# PCB_WiFiModule_to_Xbee_rev0_2.net
KiCad netlist of a schematic drawn in EAGLE
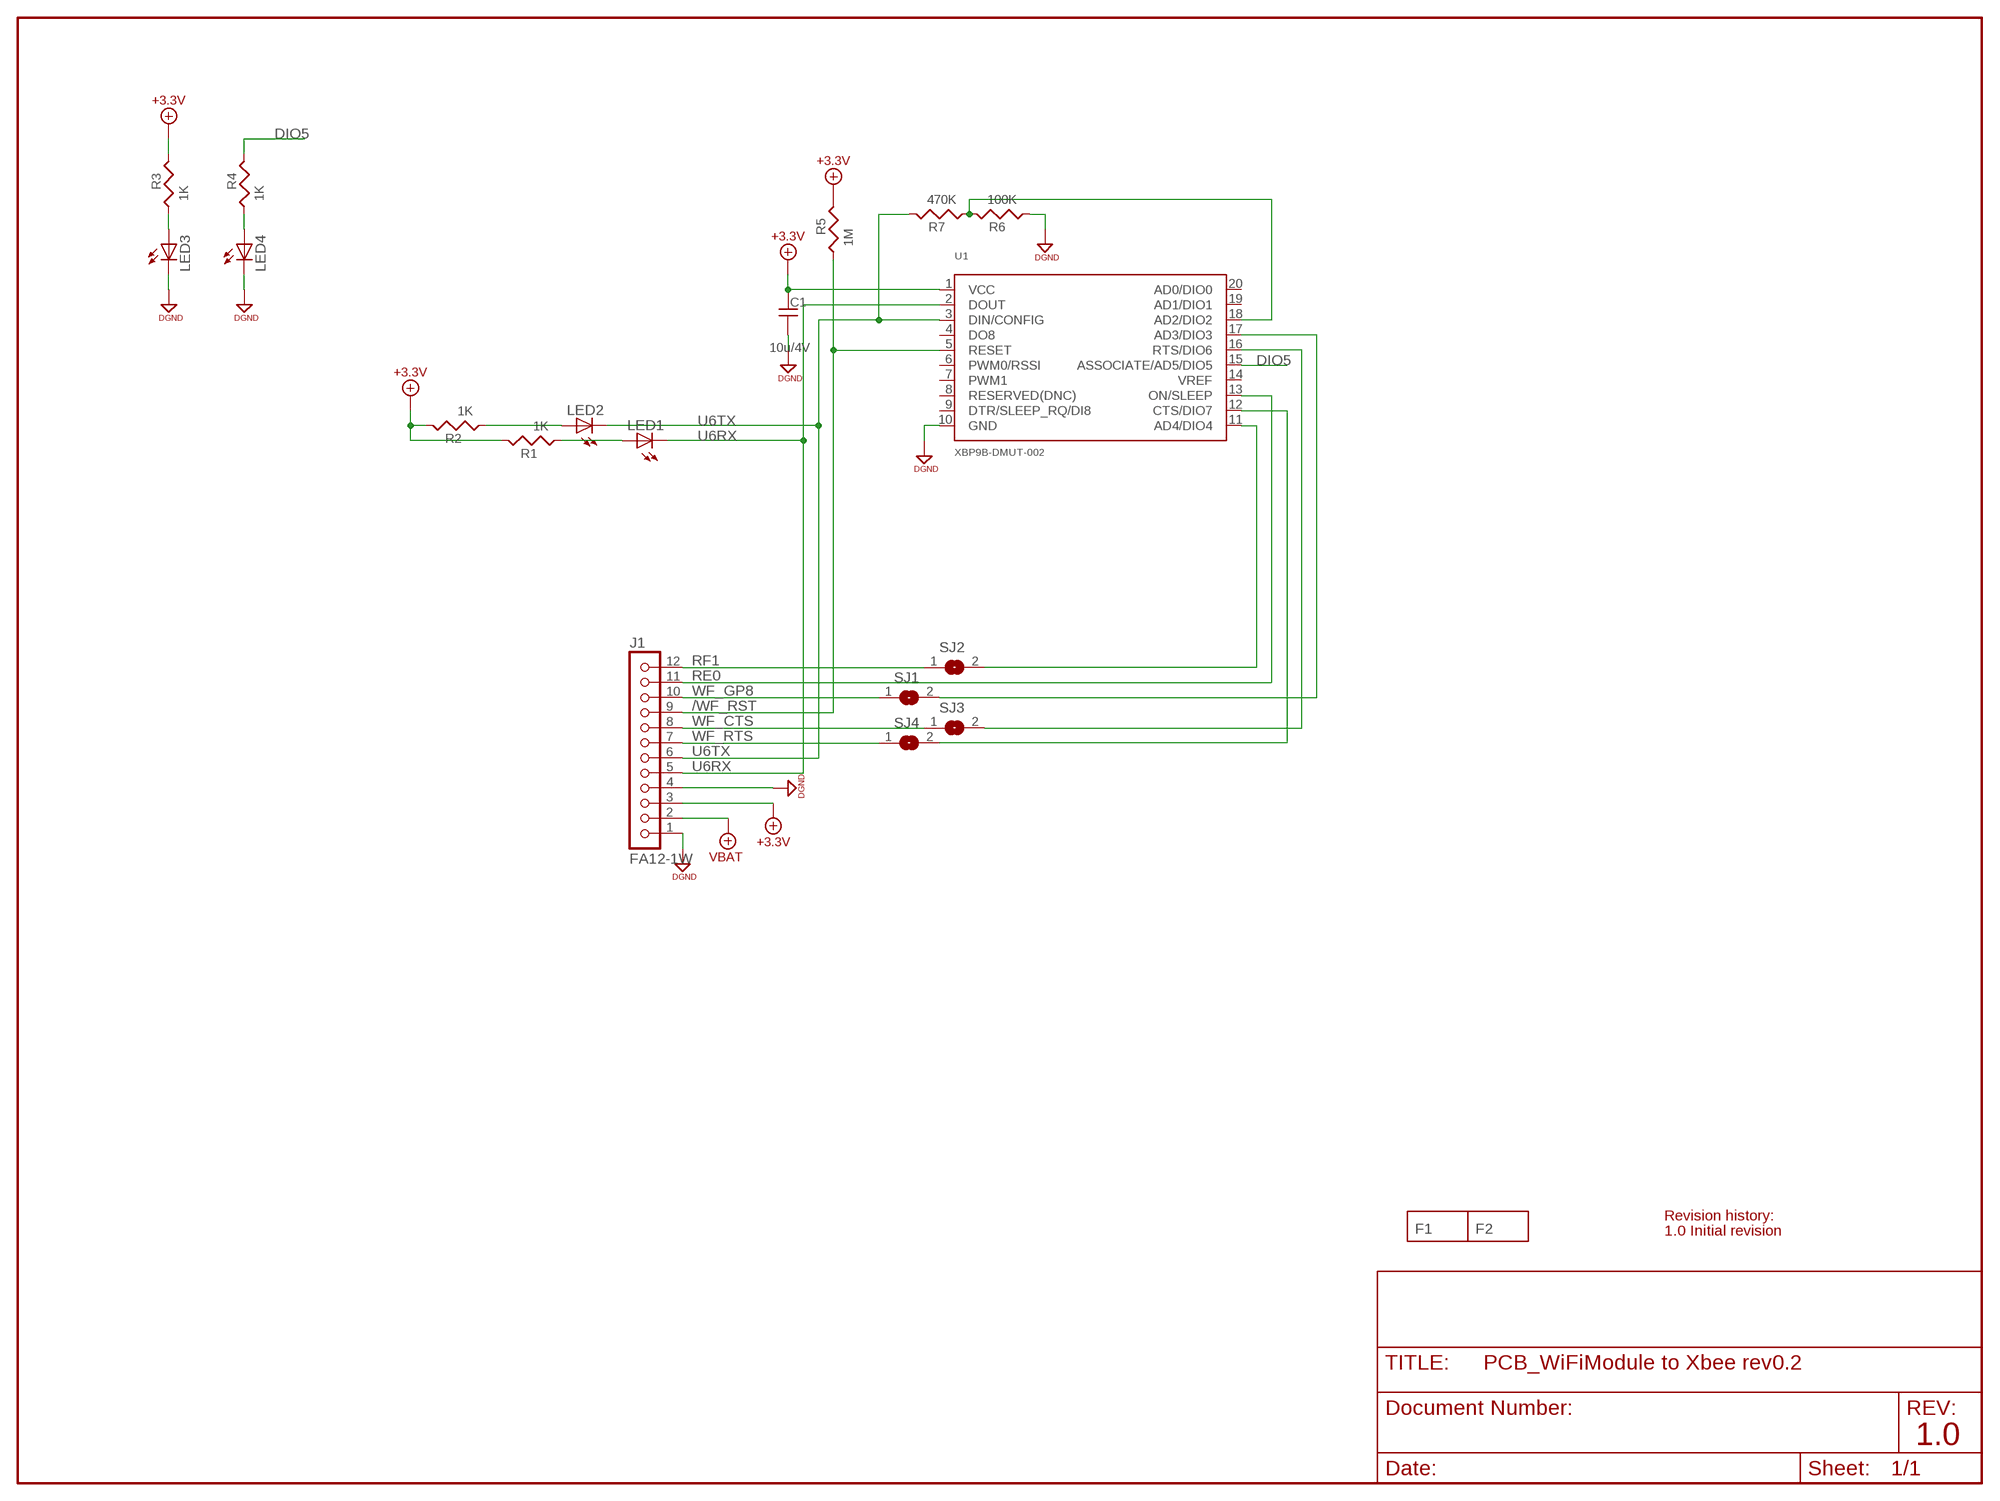
[diagram p0: schematic, sheet 1]

(export (version "E")
  (design (tool "Eeschema 10.0.6"))
  (components
    (comp (ref "C1")
      (value "10u/4V")
      (footprint "eagle-import:0603")
      (libsource (lib "eagle-import") (part "C-0603"))
    )
    (comp (ref "F1")
      (value "REF")
      (footprint "eagle-import:REF")
      (libsource (lib "eagle-import") (part "REF"))
    )
    (comp (ref "F2")
      (value "REF")
      (footprint "eagle-import:REF")
      (libsource (lib "eagle-import") (part "REF"))
    )
    (comp (ref "J1")
      (value "FA12-1W")
      (footprint "eagle-import:FA12-1W")
      (libsource (lib "eagle-import") (part "FA12-1W"))
    )
    (comp (ref "LED1")
      (value "LEDCHIP-LED0603")
      (footprint "eagle-import:CHIP-LED0603")
      (libsource (lib "eagle-import") (part "LEDCHIP-LED0603"))
    )
    (comp (ref "LED2")
      (value "LEDCHIP-LED0603")
      (footprint "eagle-import:CHIP-LED0603")
      (libsource (lib "eagle-import") (part "LEDCHIP-LED0603"))
    )
    (comp (ref "LED3")
      (value "LEDCHIP-LED0603")
      (footprint "eagle-import:CHIP-LED0603")
      (libsource (lib "eagle-import") (part "LEDCHIP-LED0603"))
    )
    (comp (ref "LED4")
      (value "LEDCHIP-LED0603")
      (footprint "eagle-import:CHIP-LED0603")
      (libsource (lib "eagle-import") (part "LEDCHIP-LED0603"))
    )
    (comp (ref "R1")
      (value "1K")
      (footprint "eagle-import:0603")
      (libsource (lib "eagle-import") (part "R-0603"))
    )
    (comp (ref "R2")
      (value "1K")
      (footprint "eagle-import:0603")
      (libsource (lib "eagle-import") (part "R-0603"))
    )
    (comp (ref "R3")
      (value "1K")
      (footprint "eagle-import:0603")
      (libsource (lib "eagle-import") (part "R-0603"))
    )
    (comp (ref "R4")
      (value "1K")
      (footprint "eagle-import:0603")
      (libsource (lib "eagle-import") (part "R-0603"))
    )
    (comp (ref "R5")
      (value "1M")
      (footprint "eagle-import:0603")
      (libsource (lib "eagle-import") (part "R-0603"))
    )
    (comp (ref "R6")
      (value "100K")
      (footprint "eagle-import:0603")
      (libsource (lib "eagle-import") (part "R-0603"))
    )
    (comp (ref "R7")
      (value "470K")
      (footprint "eagle-import:0603")
      (libsource (lib "eagle-import") (part "R-0603"))
    )
    (comp (ref "SJ1") (value "SJ") (footprint "eagle-import:SJ") (libsource (lib "eagle-import") (part "SJ")))
    (comp (ref "SJ2") (value "SJ") (footprint "eagle-import:SJ") (libsource (lib "eagle-import") (part "SJ")))
    (comp (ref "SJ3") (value "SJ") (footprint "eagle-import:SJ") (libsource (lib "eagle-import") (part "SJ")))
    (comp (ref "SJ4") (value "SJ") (footprint "eagle-import:SJ") (libsource (lib "eagle-import") (part "SJ")))
    (comp (ref "U1")
      (value "XBP9B-DMUT-002")
      (footprint "eagle-import:XBP9B-DMUT-002")
      (libsource (lib "eagle-import") (part "XBP9B-DMUT-002"))
    )
  )
  (nets
    (net (code "1") (name "+3.3V") (class "Default")
      (node (ref "C1") (pin "1") (pinfunction "1_1") (pintype "passive"))
      (node (ref "J1") (pin "3") (pinfunction "3_3") (pintype "passive"))
      (node (ref "R1") (pin "2") (pinfunction "2_2") (pintype "passive"))
      (node (ref "R2") (pin "2") (pinfunction "2_2") (pintype "passive"))
      (node (ref "R3") (pin "2") (pinfunction "2_2") (pintype "passive"))
      (node (ref "R5") (pin "2") (pinfunction "2_2") (pintype "passive"))
      (node (ref "U1") (pin "1") (pinfunction "VCC_1") (pintype "bidirectional"))
    )
    (net (code "2") (name "/DIO5") (class "Default")
      (node (ref "R4") (pin "2") (pinfunction "2_2") (pintype "passive"))
      (node (ref "U1") (pin "15") (pinfunction "ASSOCIATE/AD5/DIO5_15") (pintype "bidirectional"))
    )
    (net (code "3") (name "/RE0") (class "Default")
      (node (ref "J1") (pin "11") (pinfunction "11_11") (pintype "passive"))
      (node (ref "U1") (pin "13") (pinfunction "ON/SLEEP_13") (pintype "bidirectional"))
    )
    (net (code "4") (name "/RF1") (class "Default")
      (node (ref "J1") (pin "12") (pinfunction "12_12") (pintype "passive"))
      (node (ref "SJ2") (pin "1") (pinfunction "1_1") (pintype "passive"))
    )
    (net (code "5") (name "/U6RX") (class "Default")
      (node (ref "J1") (pin "5") (pinfunction "5_5") (pintype "passive"))
      (node (ref "LED1") (pin "C") (pinfunction "C_C") (pintype "passive"))
      (node (ref "U1") (pin "2") (pinfunction "DOUT_2") (pintype "bidirectional"))
    )
    (net (code "6") (name "/U6TX") (class "Default")
      (node (ref "J1") (pin "6") (pinfunction "6_6") (pintype "passive"))
      (node (ref "LED2") (pin "C") (pinfunction "C_C") (pintype "passive"))
      (node (ref "R7") (pin "2") (pinfunction "2_2") (pintype "passive"))
      (node (ref "U1") (pin "3") (pinfunction "DIN/CONFIG_3") (pintype "bidirectional"))
    )
    (net (code "7") (name "/WF_CTS") (class "Default")
      (node (ref "J1") (pin "8") (pinfunction "8_8") (pintype "passive"))
      (node (ref "SJ3") (pin "1") (pinfunction "1_1") (pintype "passive"))
    )
    (net (code "8") (name "/WF_GP8") (class "Default")
      (node (ref "J1") (pin "10") (pinfunction "10_10") (pintype "passive"))
      (node (ref "SJ1") (pin "1") (pinfunction "1_1") (pintype "passive"))
    )
    (net (code "9") (name "/WF_RTS") (class "Default")
      (node (ref "J1") (pin "7") (pinfunction "7_7") (pintype "passive"))
      (node (ref "SJ4") (pin "1") (pinfunction "1_1") (pintype "passive"))
    )
    (net (code "10") (name "/{slash}WF_RST") (class "Default")
      (node (ref "J1") (pin "9") (pinfunction "9_9") (pintype "passive"))
      (node (ref "R5") (pin "1") (pinfunction "1_1") (pintype "passive"))
      (node (ref "U1") (pin "5") (pinfunction "RESET_5") (pintype "bidirectional"))
    )
    (net (code "11") (name "DGND") (class "Default")
      (node (ref "C1") (pin "2") (pinfunction "2_2") (pintype "passive"))
      (node (ref "J1") (pin "1") (pinfunction "1_1") (pintype "passive"))
      (node (ref "J1") (pin "4") (pinfunction "4_4") (pintype "passive"))
      (node (ref "LED3") (pin "C") (pinfunction "C_C") (pintype "passive"))
      (node (ref "LED4") (pin "C") (pinfunction "C_C") (pintype "passive"))
      (node (ref "R6") (pin "1") (pinfunction "1_1") (pintype "passive"))
      (node (ref "U1") (pin "10") (pinfunction "GND_10") (pintype "bidirectional"))
    )
    (net (code "12") (name "Net-(LED1-PadA)") (class "Default")
      (node (ref "LED1") (pin "A") (pinfunction "A_A") (pintype "passive"))
      (node (ref "R1") (pin "1") (pinfunction "1_1") (pintype "passive"))
    )
    (net (code "13") (name "Net-(LED2-PadA)") (class "Default")
      (node (ref "LED2") (pin "A") (pinfunction "A_A") (pintype "passive"))
      (node (ref "R2") (pin "1") (pinfunction "1_1") (pintype "passive"))
    )
    (net (code "14") (name "Net-(LED3-PadA)") (class "Default")
      (node (ref "LED3") (pin "A") (pinfunction "A_A") (pintype "passive"))
      (node (ref "R3") (pin "1") (pinfunction "1_1") (pintype "passive"))
    )
    (net (code "15") (name "Net-(LED4-PadA)") (class "Default")
      (node (ref "LED4") (pin "A") (pinfunction "A_A") (pintype "passive"))
      (node (ref "R4") (pin "1") (pinfunction "1_1") (pintype "passive"))
    )
    (net (code "16") (name "Net-(U1-AD2{slash}DIO2)") (class "Default")
      (node (ref "R6") (pin "2") (pinfunction "2_2") (pintype "passive"))
      (node (ref "R7") (pin "1") (pinfunction "1_1") (pintype "passive"))
      (node (ref "U1") (pin "18") (pinfunction "AD2/DIO2_18") (pintype "bidirectional"))
    )
    (net (code "17") (name "Net-(U1-AD3{slash}DIO3)") (class "Default")
      (node (ref "SJ1") (pin "2") (pinfunction "2_2") (pintype "passive"))
      (node (ref "U1") (pin "17") (pinfunction "AD3/DIO3_17") (pintype "bidirectional"))
    )
    (net (code "18") (name "Net-(U1-AD4{slash}DIO4)") (class "Default")
      (node (ref "SJ2") (pin "2") (pinfunction "2_2") (pintype "passive"))
      (node (ref "U1") (pin "11") (pinfunction "AD4/DIO4_11") (pintype "bidirectional"))
    )
    (net (code "19") (name "Net-(U1-CTS{slash}DIO7)") (class "Default")
      (node (ref "SJ4") (pin "2") (pinfunction "2_2") (pintype "passive"))
      (node (ref "U1") (pin "12") (pinfunction "CTS/DIO7_12") (pintype "bidirectional"))
    )
    (net (code "20") (name "Net-(U1-RTS{slash}DIO6)") (class "Default")
      (node (ref "SJ3") (pin "2") (pinfunction "2_2") (pintype "passive"))
      (node (ref "U1") (pin "16") (pinfunction "RTS/DIO6_16") (pintype "bidirectional"))
    )
    (net (code "21") (name "VBAT") (class "Default")
      (node (ref "J1") (pin "2") (pinfunction "2_2") (pintype "passive"))
    )
    (net (code "22") (name "unconnected-(U1-AD0{slash}DIO0-Pad20)") (class "Default")
      (node (ref "U1") (pin "20") (pinfunction "AD0/DIO0_20") (pintype "bidirectional"))
    )
    (net (code "23") (name "unconnected-(U1-AD1{slash}DIO1-Pad19)") (class "Default")
      (node (ref "U1") (pin "19") (pinfunction "AD1/DIO1_19") (pintype "bidirectional"))
    )
    (net (code "24") (name "unconnected-(U1-DO8-Pad4)") (class "Default")
      (node (ref "U1") (pin "4") (pinfunction "DO8_4") (pintype "bidirectional"))
    )
    (net (code "25") (name "unconnected-(U1-DTR{slash}SLEEP_RQ{slash}DI8-Pad9)") (class "Default")
      (node (ref "U1") (pin "9") (pinfunction "DTR/SLEEP_RQ/DI8_9") (pintype "bidirectional"))
    )
    (net (code "26") (name "unconnected-(U1-PWM0{slash}RSSI-Pad6)") (class "Default")
      (node (ref "U1") (pin "6") (pinfunction "PWM0/RSSI_6") (pintype "bidirectional"))
    )
    (net (code "27") (name "unconnected-(U1-PWM1-Pad7)") (class "Default")
      (node (ref "U1") (pin "7") (pinfunction "PWM1_7") (pintype "bidirectional"))
    )
    (net (code "28") (name "unconnected-(U1-RESERVED(DNC)-Pad8)") (class "Default")
      (node (ref "U1") (pin "8") (pinfunction "RESERVED(DNC)_8") (pintype "bidirectional"))
    )
    (net (code "29") (name "unconnected-(U1-VREF-Pad14)") (class "Default")
      (node (ref "U1") (pin "14") (pinfunction "VREF_14") (pintype "bidirectional"))
    )
  )
)
